# AICat_V1_2.net
KiCad netlist of a schematic drawn in Altium Designer
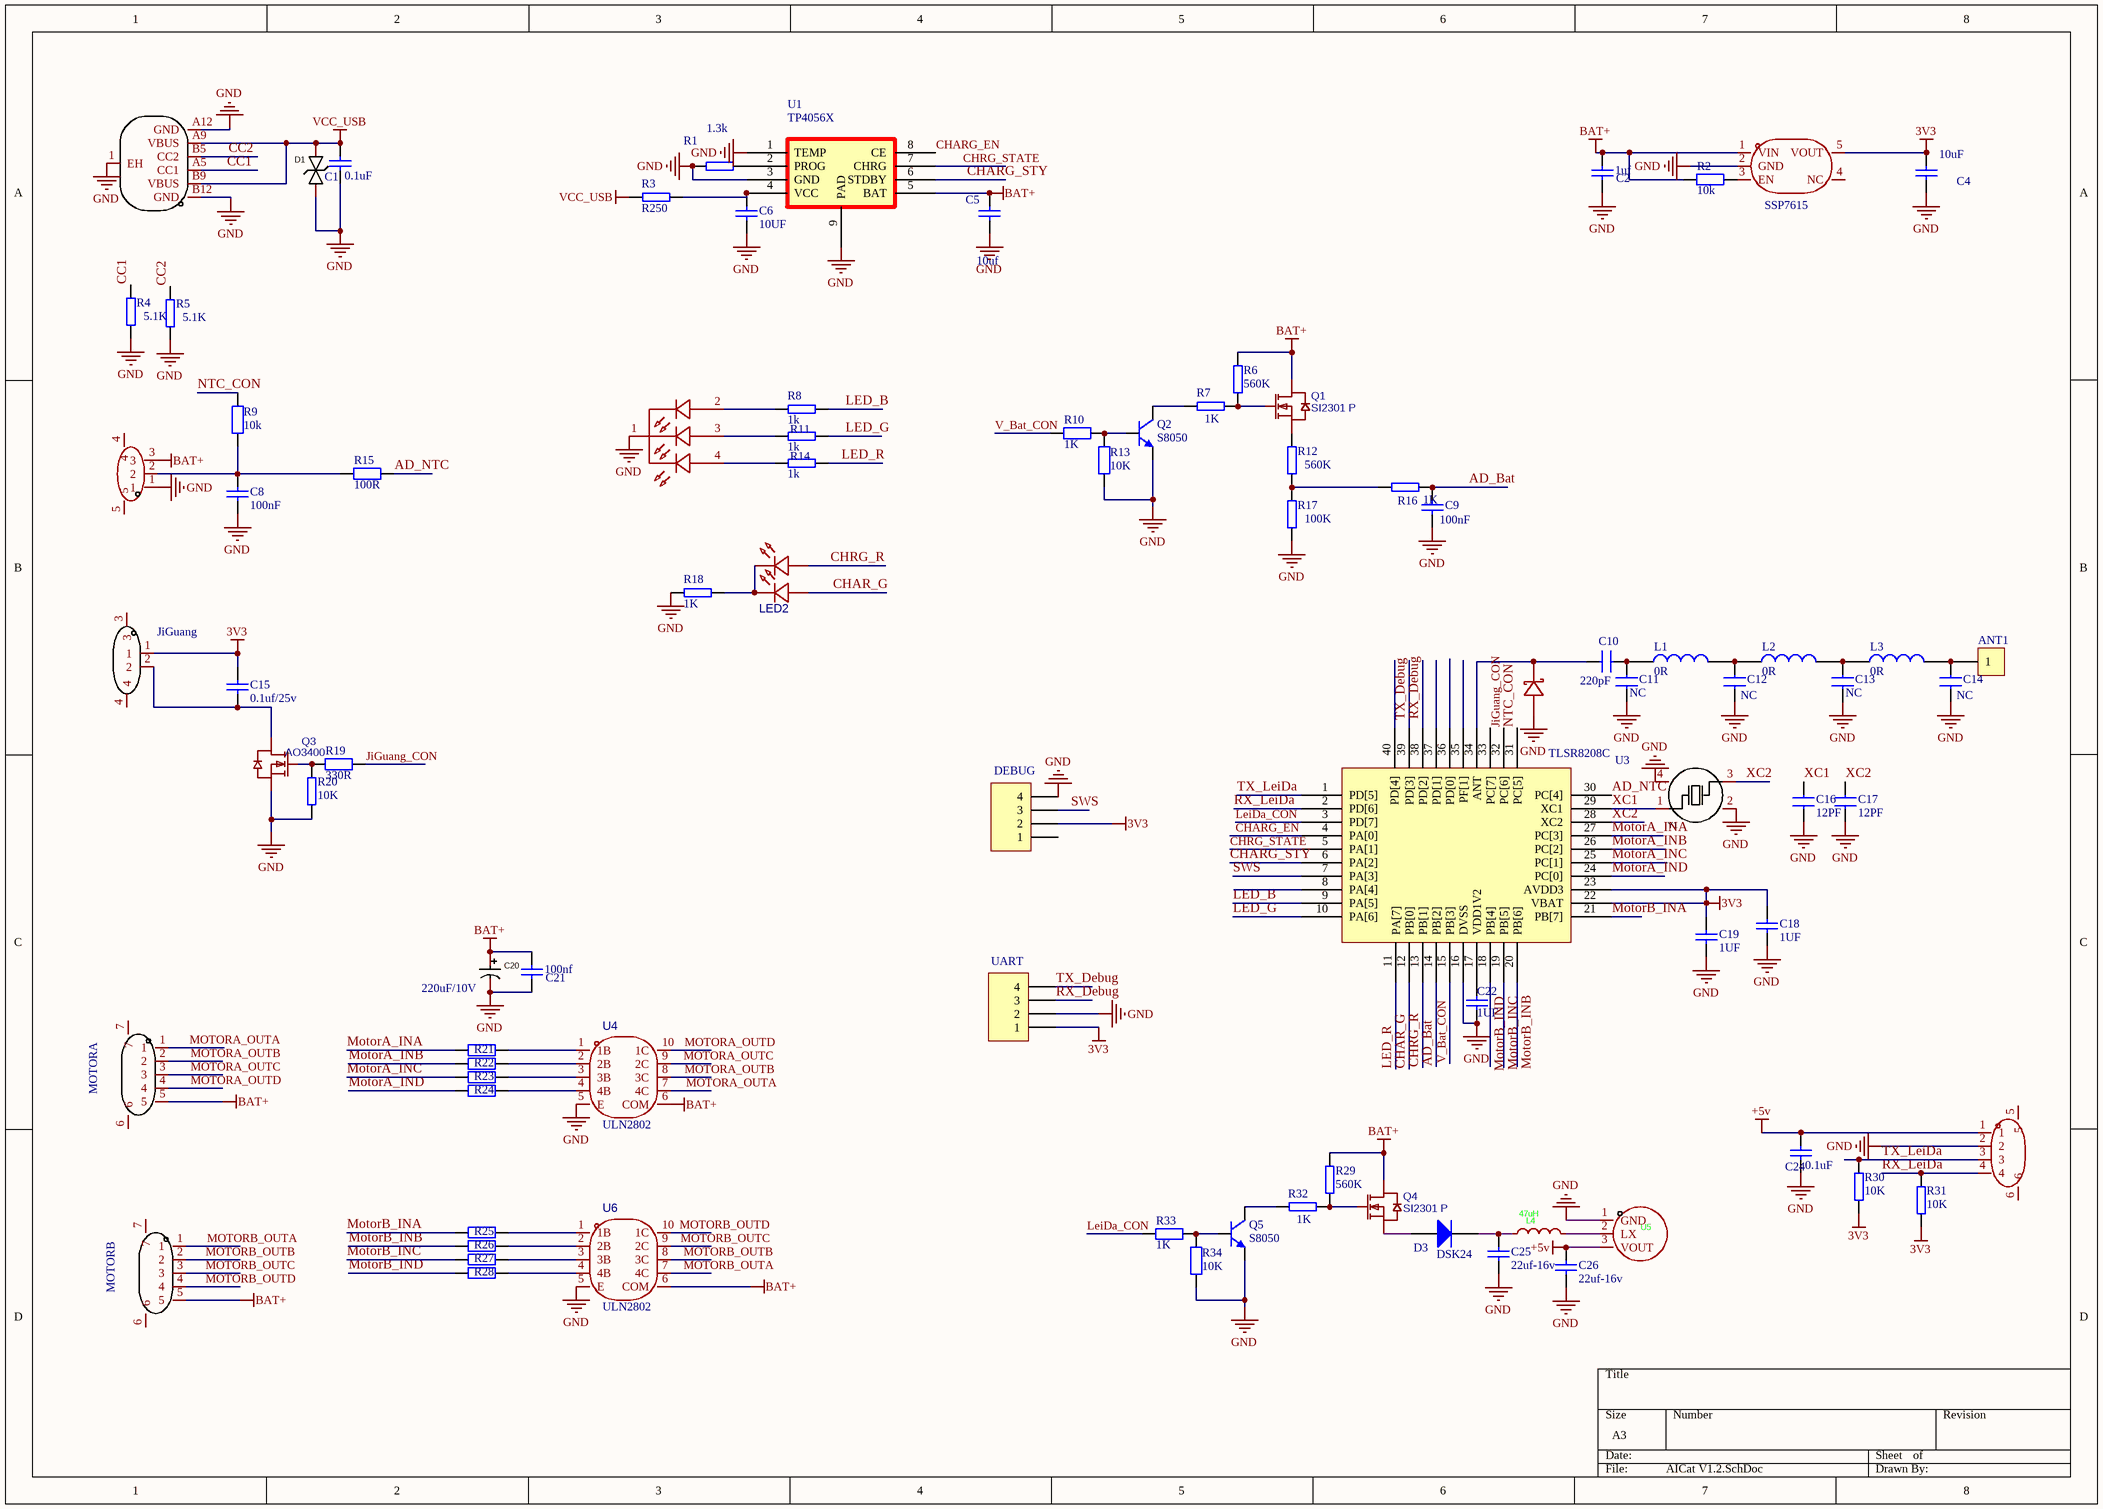
[diagram p0: AICat V1.2.SchDoc]

(export (version "E")
  (design (tool "Eeschema 10.0.6"))
  (components
    (comp (ref "ANT1")
      (value "~")
      (footprint "tp")
      (description "Connector")
      (libsource (lib "*") (part "CON1"))
    )
    (comp (ref "BAT1")
      (value "BX-PH2.0-3PWT")
      (footprint "HDR-TH_3P-P2.50_ZX-XH2.54-3PWZ")
      (libsource (lib "altium-import") (part "root_2_BX-PH2.0-3PWT_"))
    )
    (comp (ref "C1")
      (value "0.1uF")
      (footprint "0603_C")
      (description "Capacitor")
      (fields (field (name "PUBLISHER") "Altium Limited"))
      (libsource (lib "*") (part "Cap"))
    )
    (comp (ref "C2")
      (value "1uf")
      (footprint "0603_C")
      (description "无极电容")
      (libsource (lib "电容电阻电感保险") (part "Cap1"))
    )
    (comp (ref "C4")
      (value "10uF")
      (footprint "0603_C")
      (description "Capacitor")
      (fields (field (name "PUBLISHER") "Altium Limited"))
      (libsource (lib "*") (part "Cap"))
    )
    (comp (ref "C5")
      (value "10uf")
      (footprint "0603_C")
      (description "Capacitor")
      (fields (field (name "PUBLISHER") "Altium Limited"))
      (libsource (lib "*") (part "Cap"))
    )
    (comp (ref "C6") (value "10UF") (footprint "0603_c") (libsource (lib "DIY") (part "CAP")))
    (comp (ref "C8") (value "100nF") (footprint "0603_C") (libsource (lib "DIY") (part "CAP")))
    (comp (ref "C9") (value "100nF") (footprint "0603_C") (libsource (lib "DIY") (part "CAP")))
    (comp (ref "C10")
      (value "220pF")
      (footprint "0402_c")
      (description "Capacitor")
      (libsource (lib "*") (part "CAP"))
    )
    (comp (ref "C11")
      (value "NC")
      (footprint "0402_C")
      (description "Capacitor")
      (libsource (lib "*") (part "CAP"))
    )
    (comp (ref "C12")
      (value "NC")
      (footprint "0402_C")
      (description "Capacitor")
      (libsource (lib "*") (part "CAP"))
    )
    (comp (ref "C13")
      (value "NC")
      (footprint "0402_C")
      (description "Capacitor")
      (libsource (lib "*") (part "CAP"))
    )
    (comp (ref "C14")
      (value "NC")
      (footprint "0402_C")
      (description "Capacitor")
      (libsource (lib "*") (part "CAP"))
    )
    (comp (ref "C15")
      (value "0.1uf/25v")
      (footprint "0603_C")
      (description "Capacitor")
      (fields (field (name "PUBLISHER") "Altium Limited"))
      (libsource (lib "*") (part "Cap"))
    )
    (comp (ref "C16")
      (value "12PF")
      (footprint "0603_c")
      (description "Capacitor")
      (libsource (lib "*") (part "CAP"))
    )
    (comp (ref "C17")
      (value "12PF")
      (footprint "0603_c")
      (description "Capacitor")
      (libsource (lib "*") (part "CAP"))
    )
    (comp (ref "C18") (value "1UF") (footprint "0603_c") (libsource (lib "DIY") (part "CAP")))
    (comp (ref "C19") (value "1UF") (footprint "0603_c") (libsource (lib "DIY") (part "CAP")))
    (comp (ref "C20")
      (value "220uF/10V")
      (footprint "SMD 6.3*5.4 电解")
      (fields (field (name "MANUFACTURER PART") "RVT1A221M0605"))
      (libsource (lib "altium-import") (part "root_0_RVT1A221M0605_C72494_"))
    )
    (comp (ref "C21")
      (value "100nf")
      (footprint "0603_C")
      (description "无极电容")
      (libsource (lib "电容电阻电感保险") (part "Cap1"))
    )
    (comp (ref "C22") (value "1UF") (footprint "0603_c") (libsource (lib "DIY") (part "CAP")))
    (comp (ref "C24")
      (value "0.1uF")
      (footprint "0603_C")
      (description "Capacitor")
      (fields (field (name "PUBLISHER") "Altium Limited"))
      (libsource (lib "*") (part "Cap"))
    )
    (comp (ref "C25")
      (value "22uf-16v")
      (footprint "0805_c")
      (description "无极电容")
      (libsource (lib "电容电阻电感保险") (part "Cap1"))
    )
    (comp (ref "C26")
      (value "22uf-16v")
      (footprint "0805_c")
      (description "无极电容")
      (libsource (lib "电容电阻电感保险") (part "Cap1"))
    )
    (comp (ref "CN1")
      (value "JiGuang")
      (footprint "CONN-SMD_2P-P1.25-LT")
      (fields (field (name "MANUFACTURER PART") "HC-1.25-2PLT"))
      (libsource (lib "altium-import") (part "root_0_mirrored_HC-1.25-2PLT_"))
    )
    (comp (ref "CN2")
      (value "HC-1.25-4PLT")
      (footprint "CONN-SMD_4P-P1.25_LT")
      (libsource (lib "altium-import") (part "root_0_HC-1.25-4PLT_"))
    )
    (comp (ref "D1")
      (value "SMF5.0CA_C726939")
      (footprint "SOD-123 双向")
      (fields (field (name "MANUFACTURER PART") "SMF5.0CA"))
      (libsource (lib "altium-import") (part "root_1_SMF5.0CA_C726939_"))
    )
    (comp (ref "D2")
      (value "SE6V3LHN102T 6.3v单向")
      (footprint "0402-D")
      (libsource (lib "altium-import") (part "root_3_TPNSR05F20NXT5G_"))
    )
    (comp (ref "D3")
      (value "DSK24")
      (footprint "SOD-123FL")
      (description "High Conductance Fast Diode")
      (fields (field (name "PUBLISHER") "Altium Limited"))
      (libsource (lib "Miscellaneous Devices") (part "Diode 1N4148"))
    )
    (comp (ref "J1")
      (value "MOTORA")
      (footprint "CONN-SMD_1.25-5PLT")
      (fields (field (name "MANUFACTURER PART") "HC-1.25-5PLT"))
      (libsource (lib "altium-import") (part "root_0_mirrored_HC-1.25-5PLT_"))
    )
    (comp (ref "J2")
      (value "MOTORB")
      (footprint "CONN-SMD_1.25-5PLT")
      (fields (field (name "MANUFACTURER PART") "HC-1.25-5PLT"))
      (libsource (lib "altium-import") (part "root_0_mirrored_HC-1.25-5PLT_"))
    )
    (comp (ref "L1") (value "0R") (footprint "0402_R") (libsource (lib "*") (part "INDUCTOR")))
    (comp (ref "L2") (value "0R") (footprint "0402_R") (libsource (lib "*") (part "INDUCTOR")))
    (comp (ref "L3") (value "0R") (footprint "0402_R") (libsource (lib "*") (part "INDUCTOR")))
    (comp (ref "L4")
      (value "47uH")
      (footprint "IND-SMD_L3.5-W3.0_CD31")
      (fields (field (name "MANUFACTURER PART") "CD31-470M 47UH"))
      (libsource (lib "altium-import") (part "root_0_CD31-470M 47UH_"))
    )
    (comp (ref "LED1")
      (value "XL-A3528RGBC-BM")
      (footprint "LED-ARRAY-SMD_4P-L3.2-W2.8-LS3.5-BL_XL-A3528RGBC-BM")
      (libsource (lib "altium-import") (part "root_2_XL-A3528RGBC-BM_"))
    )
    (comp (ref "LED2")
      (value "*")
      (footprint "LED-SMD_4P-L3.2-W1.6-TL_XL-3216SURUGC")
      (libsource (lib "altium-import") (part "root_0_TJ-S2012SW8TCGLC2R2G-A5_"))
    )
    (comp (ref "P1")
      (value "DEBUG")
      (footprint "SIP4-2.54")
      (description "Header, 4-Pin")
      (fields (field (name "PUBLISHER") "Altium Limited"))
      (libsource (lib "Miscellaneous Connectors") (part "Header 4"))
    )
    (comp (ref "P2")
      (value "UART")
      (footprint "SIP4-2.54")
      (description "Header, 4-Pin")
      (fields (field (name "PUBLISHER") "Altium Limited"))
      (libsource (lib "Miscellaneous Connectors") (part "Header 4"))
    )
    (comp (ref "Q1")
      (value "SI2301 P")
      (footprint "SOT-23")
      (fields
        (field (name "BOM_SUPPLIER PART") "C2890442")
        (field (name "BOM_MANUFACTURER PART") "JMTL3400A")
        (field (name "CONTRIBUTOR") "LCSC")
      )
      (libsource (lib "altium-import") (part "root_0_JMTL3400A_"))
    )
    (comp (ref "Q2")
      (value "S8050")
      (footprint "SOT-23(SOT-23-3)")
      (description "NPN三极管")
      (libsource (lib "二三极管mos可控硅") (part "NPN_sot23"))
    )
    (comp (ref "Q3")
      (value "AO3400")
      (footprint "SOT-23")
      (fields
        (field (name "BOM_SUPPLIER PART") "C2890442")
        (field (name "BOM_MANUFACTURER PART") "JMTL3400A")
        (field (name "CONTRIBUTOR") "LCSC")
      )
      (libsource (lib "altium-import") (part "root_0_mirrored_JMTL3400A_"))
    )
    (comp (ref "Q4")
      (value "SI2301 P")
      (footprint "SOT-23")
      (fields
        (field (name "BOM_SUPPLIER PART") "C2890442")
        (field (name "BOM_MANUFACTURER PART") "JMTL3400A")
        (field (name "CONTRIBUTOR") "LCSC")
      )
      (libsource (lib "altium-import") (part "root_0_JMTL3400A_"))
    )
    (comp (ref "Q5")
      (value "S8050")
      (footprint "SOT-23(SOT-23-3)")
      (description "NPN三极管")
      (libsource (lib "二三极管mos可控硅") (part "NPN_sot23"))
    )
    (comp (ref "R1") (value "1.3k") (footprint "0603_R") (libsource (lib "DIY") (part "RES")))
    (comp (ref "R2")
      (value "10k")
      (footprint "0603_R")
      (description "Resistor")
      (fields (field (name "PUBLISHER") "Altium Limited"))
      (libsource (lib "") (part "Res2_3"))
    )
    (comp (ref "R3") (value "R250") (footprint "1206_R") (libsource (lib "DIY") (part "RES")))
    (comp (ref "R4") (value "5.1K") (footprint "0603_R") (libsource (lib "DIY") (part "RES")))
    (comp (ref "R5") (value "5.1K") (footprint "0603_R") (libsource (lib "DIY") (part "RES")))
    (comp (ref "R6") (value "560K") (footprint "0603_R") (libsource (lib "*") (part "RES")))
    (comp (ref "R7") (value "1K") (footprint "0603_R") (libsource (lib "") (part "RES_1")))
    (comp (ref "R8") (value "1k") (footprint "0603_R") (libsource (lib "DIY") (part "RES")))
    (comp (ref "R9")
      (value "10k")
      (footprint "0603_R")
      (description "Resistor")
      (fields (field (name "PUBLISHER") "Altium Limited"))
      (libsource (lib "*") (part "Res2"))
    )
    (comp (ref "R10")
      (value "1K")
      (footprint "0603_r")
      (description "Resistor")
      (fields (field (name "PUBLISHER") "Altium Limited"))
      (libsource (lib "") (part "Res2_1"))
    )
    (comp (ref "R11") (value "1k") (footprint "0603_R") (libsource (lib "DIY") (part "RES")))
    (comp (ref "R12") (value "560K") (footprint "0603_R") (libsource (lib "DIY") (part "RES")))
    (comp (ref "R13")
      (value "10K")
      (footprint "0603_r")
      (description "Resistor")
      (fields (field (name "PUBLISHER") "Altium Limited"))
      (libsource (lib "") (part "Res2_3"))
    )
    (comp (ref "R14") (value "1k") (footprint "0603_R") (libsource (lib "DIY") (part "RES")))
    (comp (ref "R15")
      (value "100R")
      (footprint "0603_R")
      (description "Resistor")
      (fields (field (name "PUBLISHER") "Altium Limited"))
      (libsource (lib "") (part "Res2_4"))
    )
    (comp (ref "R16") (value "1K") (footprint "0603_R") (libsource (lib "DIY") (part "RES")))
    (comp (ref "R17") (value "100K") (footprint "0603_R") (libsource (lib "DIY") (part "RES")))
    (comp (ref "R18") (value "1K") (footprint "0603_R") (libsource (lib "DIY") (part "RES")))
    (comp (ref "R19")
      (value "330R")
      (footprint "0603_R")
      (description "Resistor")
      (fields (field (name "PUBLISHER") "Altium Limited"))
      (libsource (lib "*") (part "Res2"))
    )
    (comp (ref "R20") (value "10K") (footprint "0603_R") (libsource (lib "DIY") (part "RES")))
    (comp (ref "R21")
      (value "330R")
      (footprint "0603_R")
      (description "Resistor")
      (fields (field (name "PUBLISHER") "Altium Limited"))
      (libsource (lib "") (part "Res2_2"))
    )
    (comp (ref "R22")
      (value "330R")
      (footprint "0603_R")
      (description "Resistor")
      (fields (field (name "PUBLISHER") "Altium Limited"))
      (libsource (lib "") (part "Res2_2"))
    )
    (comp (ref "R23")
      (value "330R")
      (footprint "0603_R")
      (description "Resistor")
      (fields (field (name "PUBLISHER") "Altium Limited"))
      (libsource (lib "") (part "Res2_2"))
    )
    (comp (ref "R24")
      (value "330R")
      (footprint "0603_R")
      (description "Resistor")
      (fields (field (name "PUBLISHER") "Altium Limited"))
      (libsource (lib "") (part "Res2_2"))
    )
    (comp (ref "R25")
      (value "330R")
      (footprint "0603_R")
      (description "Resistor")
      (fields (field (name "PUBLISHER") "Altium Limited"))
      (libsource (lib "") (part "Res2_2"))
    )
    (comp (ref "R26")
      (value "330R")
      (footprint "0603_R")
      (description "Resistor")
      (fields (field (name "PUBLISHER") "Altium Limited"))
      (libsource (lib "") (part "Res2_2"))
    )
    (comp (ref "R27")
      (value "330R")
      (footprint "0603_R")
      (description "Resistor")
      (fields (field (name "PUBLISHER") "Altium Limited"))
      (libsource (lib "") (part "Res2_2"))
    )
    (comp (ref "R28")
      (value "330R")
      (footprint "0603_R")
      (description "Resistor")
      (fields (field (name "PUBLISHER") "Altium Limited"))
      (libsource (lib "") (part "Res2_2"))
    )
    (comp (ref "R29") (value "560K") (footprint "0603_R") (libsource (lib "*") (part "RES")))
    (comp (ref "R30") (value "10K") (footprint "0603_R") (libsource (lib "*") (part "RES")))
    (comp (ref "R31") (value "10K") (footprint "0603_R") (libsource (lib "*") (part "RES")))
    (comp (ref "R32") (value "1K") (footprint "0603_R") (libsource (lib "") (part "RES_1")))
    (comp (ref "R33")
      (value "1K")
      (footprint "0603_r")
      (description "Resistor")
      (fields (field (name "PUBLISHER") "Altium Limited"))
      (libsource (lib "") (part "Res2_1"))
    )
    (comp (ref "R34")
      (value "10K")
      (footprint "0603_r")
      (description "Resistor")
      (fields (field (name "PUBLISHER") "Altium Limited"))
      (libsource (lib "") (part "Res2_3"))
    )
    (comp (ref "U1")
      (value "TP4056X")
      (footprint "SOP8-9")
      (description "TP4056")
      (libsource (lib "芯片") (part "TP4056"))
    )
    (comp (ref "U2")
      (value "SSP7615")
      (footprint "SOT-23-5")
      (libsource (lib "altium-import") (part "root_0_SSP7615-33M5R_"))
    )
    (comp (ref "U3")
      (value "TLSR8208C")
      (footprint "QFN-40_L5.0-W5.0-P0.40-BL-EP3.7")
      (libsource (lib "MyLib") (part "TLSR8208C"))
    )
    (comp (ref "U4")
      (value "ULN2802")
      (footprint "ESSOP-10")
      (libsource (lib "altium-import") (part "root_0_ULN2802_C2828555_"))
    )
    (comp (ref "U5")
      (value "HE9116A50NR")
      (footprint "SOT-23")
      (libsource (lib "altium-import") (part "root_0_HE9116A50NR_"))
    )
    (comp (ref "U6")
      (value "ULN2802")
      (footprint "ESSOP-10")
      (libsource (lib "altium-import") (part "root_0_ULN2802_C2828555_"))
    )
    (comp (ref "USB1")
      (value "TYPE-C 6P")
      (footprint "TPYE-C-6")
      (fields (field (name "MANUFACTURER PART") "TYPE-C 6P LTH6.5"))
      (libsource (lib "altium-import") (part "root_2_TYPE-C 6P LTH6.5_"))
    )
    (comp (ref "Y1")
      (value "24MHz +-20PPM")
      (footprint "CRYSTAL-SMD_4P-L3.2-W2.5")
      (fields (field (name "MANUFACTURER PART") "TAXM13.56M4RLBCCT2T"))
      (libsource (lib "altium-import") (part "root_0_TAXM13.56M4RLBCCT2T_"))
    )
  )
  (nets
    (net (code "1") (name "+5v") (class "Default")
      (node (ref "C24") (pin "2") (pinfunction "2_2") (pintype "passive"))
      (node (ref "C26") (pin "1") (pinfunction "1_1") (pintype "passive"))
      (node (ref "CN2") (pin "1") (pinfunction "1_1") (pintype "passive"))
      (node (ref "U5") (pin "3") (pinfunction "VOUT_3") (pintype "passive"))
    )
    (net (code "2") (name "/AD_Bat") (class "Default")
      (node (ref "C9") (pin "2") (pintype "passive"))
      (node (ref "R16") (pin "1") (pinfunction "1_1") (pintype "passive"))
      (node (ref "U3") (pin "14") (pinfunction "PB[2]_14") (pintype "passive"))
    )
    (net (code "3") (name "/AD_NTC") (class "Default")
      (node (ref "R15") (pin "1") (pinfunction "1_1") (pintype "passive"))
      (node (ref "U3") (pin "30") (pinfunction "PC[4]_30") (pintype "passive"))
    )
    (net (code "4") (name "/CC1") (class "Default")
      (node (ref "R4") (pin "1") (pinfunction "1_1") (pintype "passive"))
      (node (ref "USB1") (pin "A5") (pinfunction "CC1_A5") (pintype "passive"))
    )
    (net (code "5") (name "/CC2") (class "Default")
      (node (ref "R5") (pin "1") (pinfunction "1_1") (pintype "passive"))
      (node (ref "USB1") (pin "B5") (pinfunction "CC2_B5") (pintype "passive"))
    )
    (net (code "6") (name "/CHARG_EN") (class "Default")
      (node (ref "U1") (pin "8") (pinfunction "CE_8") (pintype "passive"))
      (node (ref "U3") (pin "4") (pinfunction "PA[0]_4") (pintype "passive"))
    )
    (net (code "7") (name "/CHARG_STY") (class "Default")
      (node (ref "U1") (pin "6") (pinfunction "STDBY_6") (pintype "passive"))
      (node (ref "U3") (pin "6") (pinfunction "PA[2]_6") (pintype "passive"))
    )
    (net (code "8") (name "/CHAR_G") (class "Default")
      (node (ref "LED2") (pin "3") (pinfunction "A_3") (pintype "passive"))
      (node (ref "U3") (pin "12") (pinfunction "PB[0]_12") (pintype "passive"))
    )
    (net (code "9") (name "/CHRG_R") (class "Default")
      (node (ref "LED2") (pin "1") (pinfunction "A_1") (pintype "passive"))
      (node (ref "U3") (pin "13") (pinfunction "PB[1]_13") (pintype "passive"))
    )
    (net (code "10") (name "/CHRG_STATE") (class "Default")
      (node (ref "U1") (pin "7") (pinfunction "CHRG_7") (pintype "passive"))
      (node (ref "U3") (pin "5") (pinfunction "PA[1]_5") (pintype "passive"))
    )
    (net (code "11") (name "/JiGuang_CON") (class "Default")
      (node (ref "R19") (pin "2") (pinfunction "2_2") (pintype "passive"))
      (node (ref "U3") (pin "32") (pinfunction "PC[6]_32") (pintype "passive"))
    )
    (net (code "12") (name "/LED_B") (class "Default")
      (node (ref "R8") (pin "2") (pinfunction "2_2") (pintype "passive"))
      (node (ref "U3") (pin "9") (pinfunction "PA[5]_9") (pintype "passive"))
    )
    (net (code "13") (name "/LED_G") (class "Default")
      (node (ref "R11") (pin "2") (pinfunction "2_2") (pintype "passive"))
      (node (ref "U3") (pin "10") (pinfunction "PA[6]_10") (pintype "passive"))
    )
    (net (code "14") (name "/LED_R") (class "Default")
      (node (ref "R14") (pin "2") (pinfunction "2_2") (pintype "passive"))
      (node (ref "U3") (pin "11") (pinfunction "PA[7]_11") (pintype "passive"))
    )
    (net (code "15") (name "/LeiDa_CON") (class "Default")
      (node (ref "R33") (pin "2") (pinfunction "2_2") (pintype "passive"))
      (node (ref "U3") (pin "3") (pinfunction "PD[7]_3") (pintype "passive"))
    )
    (net (code "16") (name "/MOTORA_OUTA") (class "Default")
      (node (ref "J1") (pin "1") (pinfunction "1_1") (pintype "passive"))
      (node (ref "U4") (pin "7") (pinfunction "4C_7") (pintype "passive"))
    )
    (net (code "17") (name "/MOTORA_OUTB") (class "Default")
      (node (ref "J1") (pin "2") (pinfunction "2_2") (pintype "passive"))
      (node (ref "U4") (pin "8") (pinfunction "3C_8") (pintype "passive"))
    )
    (net (code "18") (name "/MOTORA_OUTC") (class "Default")
      (node (ref "J1") (pin "3") (pinfunction "3_3") (pintype "passive"))
      (node (ref "U4") (pin "9") (pinfunction "2C_9") (pintype "passive"))
    )
    (net (code "19") (name "/MOTORA_OUTD") (class "Default")
      (node (ref "J1") (pin "4") (pinfunction "4_4") (pintype "passive"))
      (node (ref "U4") (pin "10") (pinfunction "1C_10") (pintype "passive"))
    )
    (net (code "20") (name "/MOTORB_OUTA") (class "Default")
      (node (ref "J2") (pin "1") (pinfunction "1_1") (pintype "passive"))
      (node (ref "U6") (pin "7") (pinfunction "4C_7") (pintype "passive"))
    )
    (net (code "21") (name "/MOTORB_OUTB") (class "Default")
      (node (ref "J2") (pin "2") (pinfunction "2_2") (pintype "passive"))
      (node (ref "U6") (pin "8") (pinfunction "3C_8") (pintype "passive"))
    )
    (net (code "22") (name "/MOTORB_OUTC") (class "Default")
      (node (ref "J2") (pin "3") (pinfunction "3_3") (pintype "passive"))
      (node (ref "U6") (pin "9") (pinfunction "2C_9") (pintype "passive"))
    )
    (net (code "23") (name "/MOTORB_OUTD") (class "Default")
      (node (ref "J2") (pin "4") (pinfunction "4_4") (pintype "passive"))
      (node (ref "U6") (pin "10") (pinfunction "1C_10") (pintype "passive"))
    )
    (net (code "24") (name "/MotorA_INA") (class "Default")
      (node (ref "R21") (pin "2") (pinfunction "2_2") (pintype "passive"))
      (node (ref "U3") (pin "27") (pinfunction "PC[3]_27") (pintype "passive"))
    )
    (net (code "25") (name "/MotorA_INB") (class "Default")
      (node (ref "R22") (pin "2") (pinfunction "2_2") (pintype "passive"))
      (node (ref "U3") (pin "26") (pinfunction "PC[2]_26") (pintype "passive"))
    )
    (net (code "26") (name "/MotorA_INC") (class "Default")
      (node (ref "R23") (pin "2") (pinfunction "2_2") (pintype "passive"))
      (node (ref "U3") (pin "25") (pinfunction "PC[1]_25") (pintype "passive"))
    )
    (net (code "27") (name "/MotorA_IND") (class "Default")
      (node (ref "R24") (pin "2") (pinfunction "2_2") (pintype "passive"))
      (node (ref "U3") (pin "24") (pinfunction "PC[0]_24") (pintype "passive"))
    )
    (net (code "28") (name "/MotorB_INA") (class "Default")
      (node (ref "R25") (pin "2") (pinfunction "2_2") (pintype "passive"))
      (node (ref "U3") (pin "21") (pinfunction "PB[7]_21") (pintype "passive"))
    )
    (net (code "29") (name "/MotorB_INB") (class "Default")
      (node (ref "R26") (pin "2") (pinfunction "2_2") (pintype "passive"))
      (node (ref "U3") (pin "20") (pinfunction "PB[6]_20") (pintype "passive"))
    )
    (net (code "30") (name "/MotorB_INC") (class "Default")
      (node (ref "R27") (pin "2") (pinfunction "2_2") (pintype "passive"))
      (node (ref "U3") (pin "19") (pinfunction "PB[5]_19") (pintype "passive"))
    )
    (net (code "31") (name "/MotorB_IND") (class "Default")
      (node (ref "R28") (pin "2") (pinfunction "2_2") (pintype "passive"))
      (node (ref "U3") (pin "18") (pinfunction "PB[4]_18") (pintype "passive"))
    )
    (net (code "32") (name "/NTC_CON") (class "Default")
      (node (ref "R9") (pin "2") (pinfunction "2_2") (pintype "passive"))
      (node (ref "U3") (pin "31") (pinfunction "PC[5]_31") (pintype "passive"))
    )
    (net (code "33") (name "/RX_Debug") (class "Default")
      (node (ref "P2") (pin "3") (pinfunction "3_3") (pintype "passive"))
      (node (ref "U3") (pin "38") (pinfunction "PD[2]_38") (pintype "passive"))
    )
    (net (code "34") (name "/RX_LeiDa") (class "Default")
      (node (ref "CN2") (pin "4") (pinfunction "4_4") (pintype "passive"))
      (node (ref "R31") (pin "1") (pintype "passive"))
      (node (ref "U3") (pin "2") (pinfunction "PD[6]_2") (pintype "passive"))
    )
    (net (code "35") (name "/SWS") (class "Default")
      (node (ref "P1") (pin "3") (pinfunction "3_3") (pintype "passive"))
      (node (ref "U3") (pin "7") (pinfunction "PA[3]_7") (pintype "passive"))
    )
    (net (code "36") (name "/TX_Debug") (class "Default")
      (node (ref "P2") (pin "4") (pinfunction "4_4") (pintype "passive"))
      (node (ref "U3") (pin "39") (pinfunction "PD[3]_39") (pintype "passive"))
    )
    (net (code "37") (name "/TX_LeiDa") (class "Default")
      (node (ref "CN2") (pin "3") (pinfunction "3_3") (pintype "passive"))
      (node (ref "R30") (pin "1") (pintype "passive"))
      (node (ref "U3") (pin "1") (pinfunction "PD[5]_1") (pintype "passive"))
    )
    (net (code "38") (name "/V_Bat_CON") (class "Default")
      (node (ref "R10") (pin "2") (pinfunction "2_2") (pintype "passive"))
      (node (ref "U3") (pin "15") (pinfunction "PB[3]_15") (pintype "passive"))
    )
    (net (code "39") (name "/XC1") (class "Default")
      (node (ref "C16") (pin "2") (pinfunction "2_2") (pintype "passive"))
      (node (ref "U3") (pin "29") (pinfunction "XC1_29") (pintype "passive"))
      (node (ref "Y1") (pin "1") (pinfunction "OSC1_1") (pintype "passive"))
    )
    (net (code "40") (name "/XC2") (class "Default")
      (node (ref "C17") (pin "2") (pinfunction "2_2") (pintype "passive"))
      (node (ref "U3") (pin "28") (pinfunction "XC2_28") (pintype "passive"))
      (node (ref "Y1") (pin "3") (pinfunction "OSC2_3") (pintype "passive"))
    )
    (net (code "41") (name "3V3") (class "Default")
      (node (ref "C15") (pin "2") (pinfunction "2_2") (pintype "passive"))
      (node (ref "C18") (pin "1") (pintype "passive"))
      (node (ref "C19") (pin "1") (pintype "passive"))
      (node (ref "C4") (pin "2") (pinfunction "2_2") (pintype "passive"))
      (node (ref "CN1") (pin "1") (pinfunction "1_1") (pintype "passive"))
      (node (ref "P1") (pin "2") (pinfunction "2_2") (pintype "passive"))
      (node (ref "P2") (pin "1") (pinfunction "1_1") (pintype "passive"))
      (node (ref "R30") (pin "2") (pintype "passive"))
      (node (ref "R31") (pin "2") (pintype "passive"))
      (node (ref "U2") (pin "5") (pinfunction "VOUT_5") (pintype "passive"))
      (node (ref "U3") (pin "22") (pinfunction "VBAT_22") (pintype "passive"))
      (node (ref "U3") (pin "23") (pinfunction "AVDD3_23") (pintype "passive"))
    )
    (net (code "42") (name "BAT+") (class "Default")
      (node (ref "BAT1") (pin "3") (pinfunction "3_3") (pintype "passive"))
      (node (ref "C2") (pin "2") (pinfunction "2_2") (pintype "passive"))
      (node (ref "C20") (pin "1") (pinfunction "1_1") (pintype "passive"))
      (node (ref "C21") (pin "2") (pinfunction "2_2") (pintype "passive"))
      (node (ref "C5") (pin "1") (pinfunction "1_1") (pintype "passive"))
      (node (ref "J1") (pin "5") (pinfunction "5_5") (pintype "passive"))
      (node (ref "J2") (pin "5") (pinfunction "5_5") (pintype "passive"))
      (node (ref "Q1") (pin "2") (pinfunction "D_2") (pintype "passive"))
      (node (ref "Q4") (pin "2") (pinfunction "D_2") (pintype "passive"))
      (node (ref "R2") (pin "1") (pinfunction "1_1") (pintype "passive"))
      (node (ref "R29") (pin "1") (pintype "passive"))
      (node (ref "R6") (pin "1") (pintype "passive"))
      (node (ref "U1") (pin "5") (pinfunction "BAT_5") (pintype "passive"))
      (node (ref "U2") (pin "1") (pinfunction "VIN_1") (pintype "passive"))
      (node (ref "U4") (pin "6") (pinfunction "COM_6") (pintype "passive"))
      (node (ref "U6") (pin "6") (pinfunction "COM_6") (pintype "passive"))
    )
    (net (code "43") (name "GND") (class "Default")
      (node (ref "BAT1") (pin "1") (pinfunction "1_1") (pintype "passive"))
      (node (ref "C1") (pin "1") (pinfunction "1_1") (pintype "passive"))
      (node (ref "C11") (pin "1") (pinfunction "1_1") (pintype "passive"))
      (node (ref "C12") (pin "1") (pinfunction "1_1") (pintype "passive"))
      (node (ref "C13") (pin "1") (pinfunction "1_1") (pintype "passive"))
      (node (ref "C14") (pin "1") (pinfunction "1_1") (pintype "passive"))
      (node (ref "C16") (pin "1") (pinfunction "1_1") (pintype "passive"))
      (node (ref "C17") (pin "1") (pinfunction "1_1") (pintype "passive"))
      (node (ref "C18") (pin "2") (pintype "passive"))
      (node (ref "C19") (pin "2") (pintype "passive"))
      (node (ref "C2") (pin "1") (pinfunction "1_1") (pintype "passive"))
      (node (ref "C20") (pin "2") (pinfunction "2_2") (pintype "passive"))
      (node (ref "C21") (pin "1") (pinfunction "1_1") (pintype "passive"))
      (node (ref "C22") (pin "1") (pintype "passive"))
      (node (ref "C24") (pin "1") (pinfunction "1_1") (pintype "passive"))
      (node (ref "C25") (pin "2") (pinfunction "2_2") (pintype "passive"))
      (node (ref "C26") (pin "2") (pinfunction "2_2") (pintype "passive"))
      (node (ref "C4") (pin "1") (pinfunction "1_1") (pintype "passive"))
      (node (ref "C5") (pin "2") (pinfunction "2_2") (pintype "passive"))
      (node (ref "C6") (pin "1") (pintype "passive"))
      (node (ref "C8") (pin "2") (pintype "passive"))
      (node (ref "C9") (pin "1") (pintype "passive"))
      (node (ref "CN2") (pin "2") (pinfunction "2_2") (pintype "passive"))
      (node (ref "D1") (pin "1") (pinfunction "1_1") (pintype "passive"))
      (node (ref "D2") (pin "2") (pinfunction "A_2") (pintype "passive"))
      (node (ref "LED1") (pin "1") (pinfunction "1_1") (pintype "passive"))
      (node (ref "P1") (pin "4") (pinfunction "4_4") (pintype "passive"))
      (node (ref "P2") (pin "2") (pinfunction "2_2") (pintype "passive"))
      (node (ref "Q2") (pin "2") (pinfunction "E_2") (pintype "passive"))
      (node (ref "Q3") (pin "2") (pinfunction "S_2") (pintype "passive"))
      (node (ref "Q5") (pin "2") (pinfunction "E_2") (pintype "passive"))
      (node (ref "R1") (pin "1") (pinfunction "1_1") (pintype "passive"))
      (node (ref "R13") (pin "1") (pinfunction "1_1") (pintype "passive"))
      (node (ref "R17") (pin "2") (pinfunction "2_2") (pintype "passive"))
      (node (ref "R18") (pin "1") (pinfunction "1_1") (pintype "passive"))
      (node (ref "R20") (pin "1") (pinfunction "1_1") (pintype "passive"))
      (node (ref "R34") (pin "1") (pinfunction "1_1") (pintype "passive"))
      (node (ref "R4") (pin "2") (pinfunction "2_2") (pintype "passive"))
      (node (ref "R5") (pin "2") (pinfunction "2_2") (pintype "passive"))
      (node (ref "U1") (pin "1") (pinfunction "TEMP_1") (pintype "passive"))
      (node (ref "U1") (pin "3") (pinfunction "GND_3") (pintype "passive"))
      (node (ref "U1") (pin "9") (pinfunction "PAD_9") (pintype "passive"))
      (node (ref "U2") (pin "2") (pinfunction "GND_2") (pintype "passive"))
      (node (ref "U3") (pin "16") (pinfunction "DVSS_16") (pintype "passive"))
      (node (ref "U4") (pin "5") (pinfunction "E_5") (pintype "passive"))
      (node (ref "U5") (pin "1") (pinfunction "GND_1") (pintype "passive"))
      (node (ref "U6") (pin "5") (pinfunction "E_5") (pintype "passive"))
      (node (ref "USB1") (pin "1") (pinfunction "EH_1") (pintype "passive"))
      (node (ref "USB1") (pin "A12") (pinfunction "GND_A12") (pintype "passive"))
      (node (ref "USB1") (pin "B12") (pinfunction "GND_B12") (pintype "passive"))
      (node (ref "Y1") (pin "2") (pinfunction "GND_2") (pintype "passive"))
      (node (ref "Y1") (pin "4") (pinfunction "GND_4") (pintype "passive"))
    )
    (net (code "44") (name "Net-(ANT1-Pad1)") (class "Default")
      (node (ref "ANT1") (pin "1") (pinfunction "1_1") (pintype "passive"))
      (node (ref "C14") (pin "2") (pinfunction "2_2") (pintype "passive"))
      (node (ref "L3") (pin "2") (pinfunction "2_2") (pintype "passive"))
    )
    (net (code "45") (name "Net-(BAT1-Pad2)") (class "Default")
      (node (ref "BAT1") (pin "2") (pinfunction "2_2") (pintype "passive"))
      (node (ref "C8") (pin "1") (pintype "passive"))
      (node (ref "R15") (pin "2") (pinfunction "2_2") (pintype "passive"))
      (node (ref "R9") (pin "1") (pinfunction "1_1") (pintype "passive"))
    )
    (net (code "46") (name "Net-(C10-Pad2)") (class "Default")
      (node (ref "C10") (pin "2") (pinfunction "2_2") (pintype "passive"))
      (node (ref "C11") (pin "2") (pinfunction "2_2") (pintype "passive"))
      (node (ref "L1") (pin "1") (pinfunction "1_1") (pintype "passive"))
    )
    (net (code "47") (name "Net-(C12-Pad2)") (class "Default")
      (node (ref "C12") (pin "2") (pinfunction "2_2") (pintype "passive"))
      (node (ref "L1") (pin "2") (pinfunction "2_2") (pintype "passive"))
      (node (ref "L2") (pin "1") (pinfunction "1_1") (pintype "passive"))
    )
    (net (code "48") (name "Net-(C13-Pad2)") (class "Default")
      (node (ref "C13") (pin "2") (pinfunction "2_2") (pintype "passive"))
      (node (ref "L2") (pin "2") (pinfunction "2_2") (pintype "passive"))
      (node (ref "L3") (pin "1") (pinfunction "1_1") (pintype "passive"))
    )
    (net (code "49") (name "Net-(D2-C)") (class "Default")
      (node (ref "C10") (pin "1") (pinfunction "1_1") (pintype "passive"))
      (node (ref "D2") (pin "1") (pinfunction "C_1") (pintype "passive"))
      (node (ref "U3") (pin "34") (pinfunction "ANT_34") (pintype "passive"))
    )
    (net (code "50") (name "Net-(D3-A)") (class "Default")
      (node (ref "D3") (pin "1") (pinfunction "A_1") (pintype "passive"))
      (node (ref "Q4") (pin "3") (pinfunction "S_3") (pintype "passive"))
    )
    (net (code "51") (name "Net-(D3-K)") (class "Default")
      (node (ref "C25") (pin "1") (pinfunction "1_1") (pintype "passive"))
      (node (ref "D3") (pin "2") (pinfunction "K_2") (pintype "passive"))
      (node (ref "L4") (pin "1") (pinfunction "1_1") (pintype "passive"))
    )
    (net (code "52") (name "Net-(LED1-Pad2)") (class "Default")
      (node (ref "LED1") (pin "2") (pinfunction "2_2") (pintype "passive"))
      (node (ref "R8") (pin "1") (pinfunction "1_1") (pintype "passive"))
    )
    (net (code "53") (name "Net-(LED1-Pad3)") (class "Default")
      (node (ref "LED1") (pin "3") (pinfunction "3_3") (pintype "passive"))
      (node (ref "R11") (pin "1") (pinfunction "1_1") (pintype "passive"))
    )
    (net (code "54") (name "Net-(LED1-Pad4)") (class "Default")
      (node (ref "LED1") (pin "4") (pinfunction "4_4") (pintype "passive"))
      (node (ref "R14") (pin "1") (pinfunction "1_1") (pintype "passive"))
    )
    (net (code "55") (name "Net-(LED2-K-Pad2)") (class "Default")
      (node (ref "LED2") (pin "2") (pinfunction "K_2") (pintype "passive"))
      (node (ref "LED2") (pin "4") (pinfunction "K_4") (pintype "passive"))
      (node (ref "R18") (pin "2") (pinfunction "2_2") (pintype "passive"))
    )
    (net (code "56") (name "Net-(Q1-G)") (class "Default")
      (node (ref "Q1") (pin "1") (pinfunction "G_1") (pintype "passive"))
      (node (ref "R6") (pin "2") (pintype "passive"))
      (node (ref "R7") (pin "1") (pintype "passive"))
    )
    (net (code "57") (name "Net-(Q1-S)") (class "Default")
      (node (ref "Q1") (pin "3") (pinfunction "S_3") (pintype "passive"))
      (node (ref "R12") (pin "1") (pinfunction "1_1") (pintype "passive"))
    )
    (net (code "58") (name "Net-(Q2-B)") (class "Default")
      (node (ref "Q2") (pin "1") (pinfunction "B_1") (pintype "passive"))
      (node (ref "R10") (pin "1") (pinfunction "1_1") (pintype "passive"))
      (node (ref "R13") (pin "2") (pinfunction "2_2") (pintype "passive"))
    )
    (net (code "59") (name "Net-(Q2-C)") (class "Default")
      (node (ref "Q2") (pin "3") (pinfunction "C_3") (pintype "passive"))
      (node (ref "R7") (pin "2") (pintype "passive"))
    )
    (net (code "60") (name "Net-(Q3-D)") (class "Default")
      (node (ref "C15") (pin "1") (pinfunction "1_1") (pintype "passive"))
      (node (ref "CN1") (pin "2") (pinfunction "2_2") (pintype "passive"))
      (node (ref "Q3") (pin "3") (pinfunction "D_3") (pintype "passive"))
    )
    (net (code "61") (name "Net-(Q3-G)") (class "Default")
      (node (ref "Q3") (pin "1") (pinfunction "G_1") (pintype "passive"))
      (node (ref "R19") (pin "1") (pinfunction "1_1") (pintype "passive"))
      (node (ref "R20") (pin "2") (pinfunction "2_2") (pintype "passive"))
    )
    (net (code "62") (name "Net-(Q4-G)") (class "Default")
      (node (ref "Q4") (pin "1") (pinfunction "G_1") (pintype "passive"))
      (node (ref "R29") (pin "2") (pintype "passive"))
      (node (ref "R32") (pin "1") (pintype "passive"))
    )
    (net (code "63") (name "Net-(Q5-B)") (class "Default")
      (node (ref "Q5") (pin "1") (pinfunction "B_1") (pintype "passive"))
      (node (ref "R33") (pin "1") (pinfunction "1_1") (pintype "passive"))
      (node (ref "R34") (pin "2") (pinfunction "2_2") (pintype "passive"))
    )
    (net (code "64") (name "Net-(Q5-C)") (class "Default")
      (node (ref "Q5") (pin "3") (pinfunction "C_3") (pintype "passive"))
      (node (ref "R32") (pin "2") (pintype "passive"))
    )
    (net (code "65") (name "Net-(R12-Pad2)") (class "Default")
      (node (ref "R12") (pin "2") (pinfunction "2_2") (pintype "passive"))
      (node (ref "R16") (pin "2") (pinfunction "2_2") (pintype "passive"))
      (node (ref "R17") (pin "1") (pinfunction "1_1") (pintype "passive"))
    )
    (net (code "66") (name "Net-(U1-PROG)") (class "Default")
      (node (ref "R1") (pin "2") (pinfunction "2_2") (pintype "passive"))
      (node (ref "U1") (pin "2") (pinfunction "PROG_2") (pintype "passive"))
    )
    (net (code "67") (name "Net-(U1-VCC)") (class "Default")
      (node (ref "C6") (pin "2") (pintype "passive"))
      (node (ref "R3") (pin "1") (pinfunction "1_1") (pintype "passive"))
      (node (ref "U1") (pin "4") (pinfunction "VCC_4") (pintype "passive"))
    )
    (net (code "68") (name "Net-(U2-EN)") (class "Default")
      (node (ref "R2") (pin "2") (pinfunction "2_2") (pintype "passive"))
      (node (ref "U2") (pin "3") (pinfunction "EN_3") (pintype "passive"))
    )
    (net (code "69") (name "Net-(U3-VDD1V2)") (class "Default")
      (node (ref "C22") (pin "2") (pintype "passive"))
      (node (ref "U3") (pin "17") (pinfunction "VDD1V2_17") (pintype "passive"))
    )
    (net (code "70") (name "Net-(U4-1B)") (class "Default")
      (node (ref "R21") (pin "1") (pinfunction "1_1") (pintype "passive"))
      (node (ref "U4") (pin "1") (pinfunction "1B_1") (pintype "passive"))
    )
    (net (code "71") (name "Net-(U4-2B)") (class "Default")
      (node (ref "R22") (pin "1") (pinfunction "1_1") (pintype "passive"))
      (node (ref "U4") (pin "2") (pinfunction "2B_2") (pintype "passive"))
    )
    (net (code "72") (name "Net-(U4-3B)") (class "Default")
      (node (ref "R23") (pin "1") (pinfunction "1_1") (pintype "passive"))
      (node (ref "U4") (pin "3") (pinfunction "3B_3") (pintype "passive"))
    )
    (net (code "73") (name "Net-(U4-4B)") (class "Default")
      (node (ref "R24") (pin "1") (pinfunction "1_1") (pintype "passive"))
      (node (ref "U4") (pin "4") (pinfunction "4B_4") (pintype "passive"))
    )
    (net (code "74") (name "Net-(U5-LX)") (class "Default")
      (node (ref "L4") (pin "2") (pinfunction "2_2") (pintype "passive"))
      (node (ref "U5") (pin "2") (pinfunction "LX_2") (pintype "passive"))
    )
    (net (code "75") (name "Net-(U6-1B)") (class "Default")
      (node (ref "R25") (pin "1") (pinfunction "1_1") (pintype "passive"))
      (node (ref "U6") (pin "1") (pinfunction "1B_1") (pintype "passive"))
    )
    (net (code "76") (name "Net-(U6-2B)") (class "Default")
      (node (ref "R26") (pin "1") (pinfunction "1_1") (pintype "passive"))
      (node (ref "U6") (pin "2") (pinfunction "2B_2") (pintype "passive"))
    )
    (net (code "77") (name "Net-(U6-3B)") (class "Default")
      (node (ref "R27") (pin "1") (pinfunction "1_1") (pintype "passive"))
      (node (ref "U6") (pin "3") (pinfunction "3B_3") (pintype "passive"))
    )
    (net (code "78") (name "Net-(U6-4B)") (class "Default")
      (node (ref "R28") (pin "1") (pinfunction "1_1") (pintype "passive"))
      (node (ref "U6") (pin "4") (pinfunction "4B_4") (pintype "passive"))
    )
    (net (code "79") (name "VCC_USB") (class "Default")
      (node (ref "C1") (pin "2") (pinfunction "2_2") (pintype "passive"))
      (node (ref "D1") (pin "2") (pinfunction "2_2") (pintype "passive"))
      (node (ref "R3") (pin "2") (pinfunction "2_2") (pintype "passive"))
      (node (ref "USB1") (pin "A9") (pinfunction "VBUS_A9") (pintype "passive"))
      (node (ref "USB1") (pin "B9") (pinfunction "VBUS_B9") (pintype "passive"))
    )
    (net (code "80") (name "unconnected-(BAT1-Pad4)") (class "Default")
      (node (ref "BAT1") (pin "4") (pinfunction "4_4") (pintype "passive"))
    )
    (net (code "81") (name "unconnected-(BAT1-Pad5)") (class "Default")
      (node (ref "BAT1") (pin "5") (pinfunction "5_5") (pintype "passive"))
    )
    (net (code "82") (name "unconnected-(CN1-Pad3)") (class "Default")
      (node (ref "CN1") (pin "3") (pinfunction "3_3") (pintype "passive"))
    )
    (net (code "83") (name "unconnected-(CN1-Pad4)") (class "Default")
      (node (ref "CN1") (pin "4") (pinfunction "4_4") (pintype "passive"))
    )
    (net (code "84") (name "unconnected-(CN2-Pad5)") (class "Default")
      (node (ref "CN2") (pin "5") (pinfunction "5_5") (pintype "passive"))
    )
    (net (code "85") (name "unconnected-(CN2-Pad6)") (class "Default")
      (node (ref "CN2") (pin "6") (pinfunction "6_6") (pintype "passive"))
    )
    (net (code "86") (name "unconnected-(J1-Pad6)") (class "Default")
      (node (ref "J1") (pin "6") (pinfunction "6_6") (pintype "passive"))
    )
    (net (code "87") (name "unconnected-(J1-Pad7)") (class "Default")
      (node (ref "J1") (pin "7") (pinfunction "7_7") (pintype "passive"))
    )
    (net (code "88") (name "unconnected-(J2-Pad6)") (class "Default")
      (node (ref "J2") (pin "6") (pinfunction "6_6") (pintype "passive"))
    )
    (net (code "89") (name "unconnected-(J2-Pad7)") (class "Default")
      (node (ref "J2") (pin "7") (pinfunction "7_7") (pintype "passive"))
    )
    (net (code "90") (name "unconnected-(P1-Pad1)") (class "Default")
      (node (ref "P1") (pin "1") (pinfunction "1_1") (pintype "passive"))
    )
    (net (code "91") (name "unconnected-(U2-NC-Pad4)") (class "Default")
      (node (ref "U2") (pin "4") (pinfunction "NC_4") (pintype "passive"))
    )
    (net (code "92") (name "unconnected-(U3-PA[4]-Pad8)") (class "Default")
      (node (ref "U3") (pin "8") (pinfunction "PA[4]_8") (pintype "passive"))
    )
    (net (code "93") (name "unconnected-(U3-PC[7]-Pad33)") (class "Default")
      (node (ref "U3") (pin "33") (pinfunction "PC[7]_33") (pintype "passive"))
    )
    (net (code "94") (name "unconnected-(U3-PD[0]-Pad36)") (class "Default")
      (node (ref "U3") (pin "36") (pinfunction "PD[0]_36") (pintype "passive"))
    )
    (net (code "95") (name "unconnected-(U3-PD[1]-Pad37)") (class "Default")
      (node (ref "U3") (pin "37") (pinfunction "PD[1]_37") (pintype "passive"))
    )
    (net (code "96") (name "unconnected-(U3-PD[4]-Pad40)") (class "Default")
      (node (ref "U3") (pin "40") (pinfunction "PD[4]_40") (pintype "passive"))
    )
    (net (code "97") (name "unconnected-(U3-PF[1]-Pad35)") (class "Default")
      (node (ref "U3") (pin "35") (pinfunction "PF[1]_35") (pintype "passive"))
    )
  )
)
